# 3w-rgb-led-connector-mk-2_0.net
KiCad netlist of a schematic drawn in EAGLE
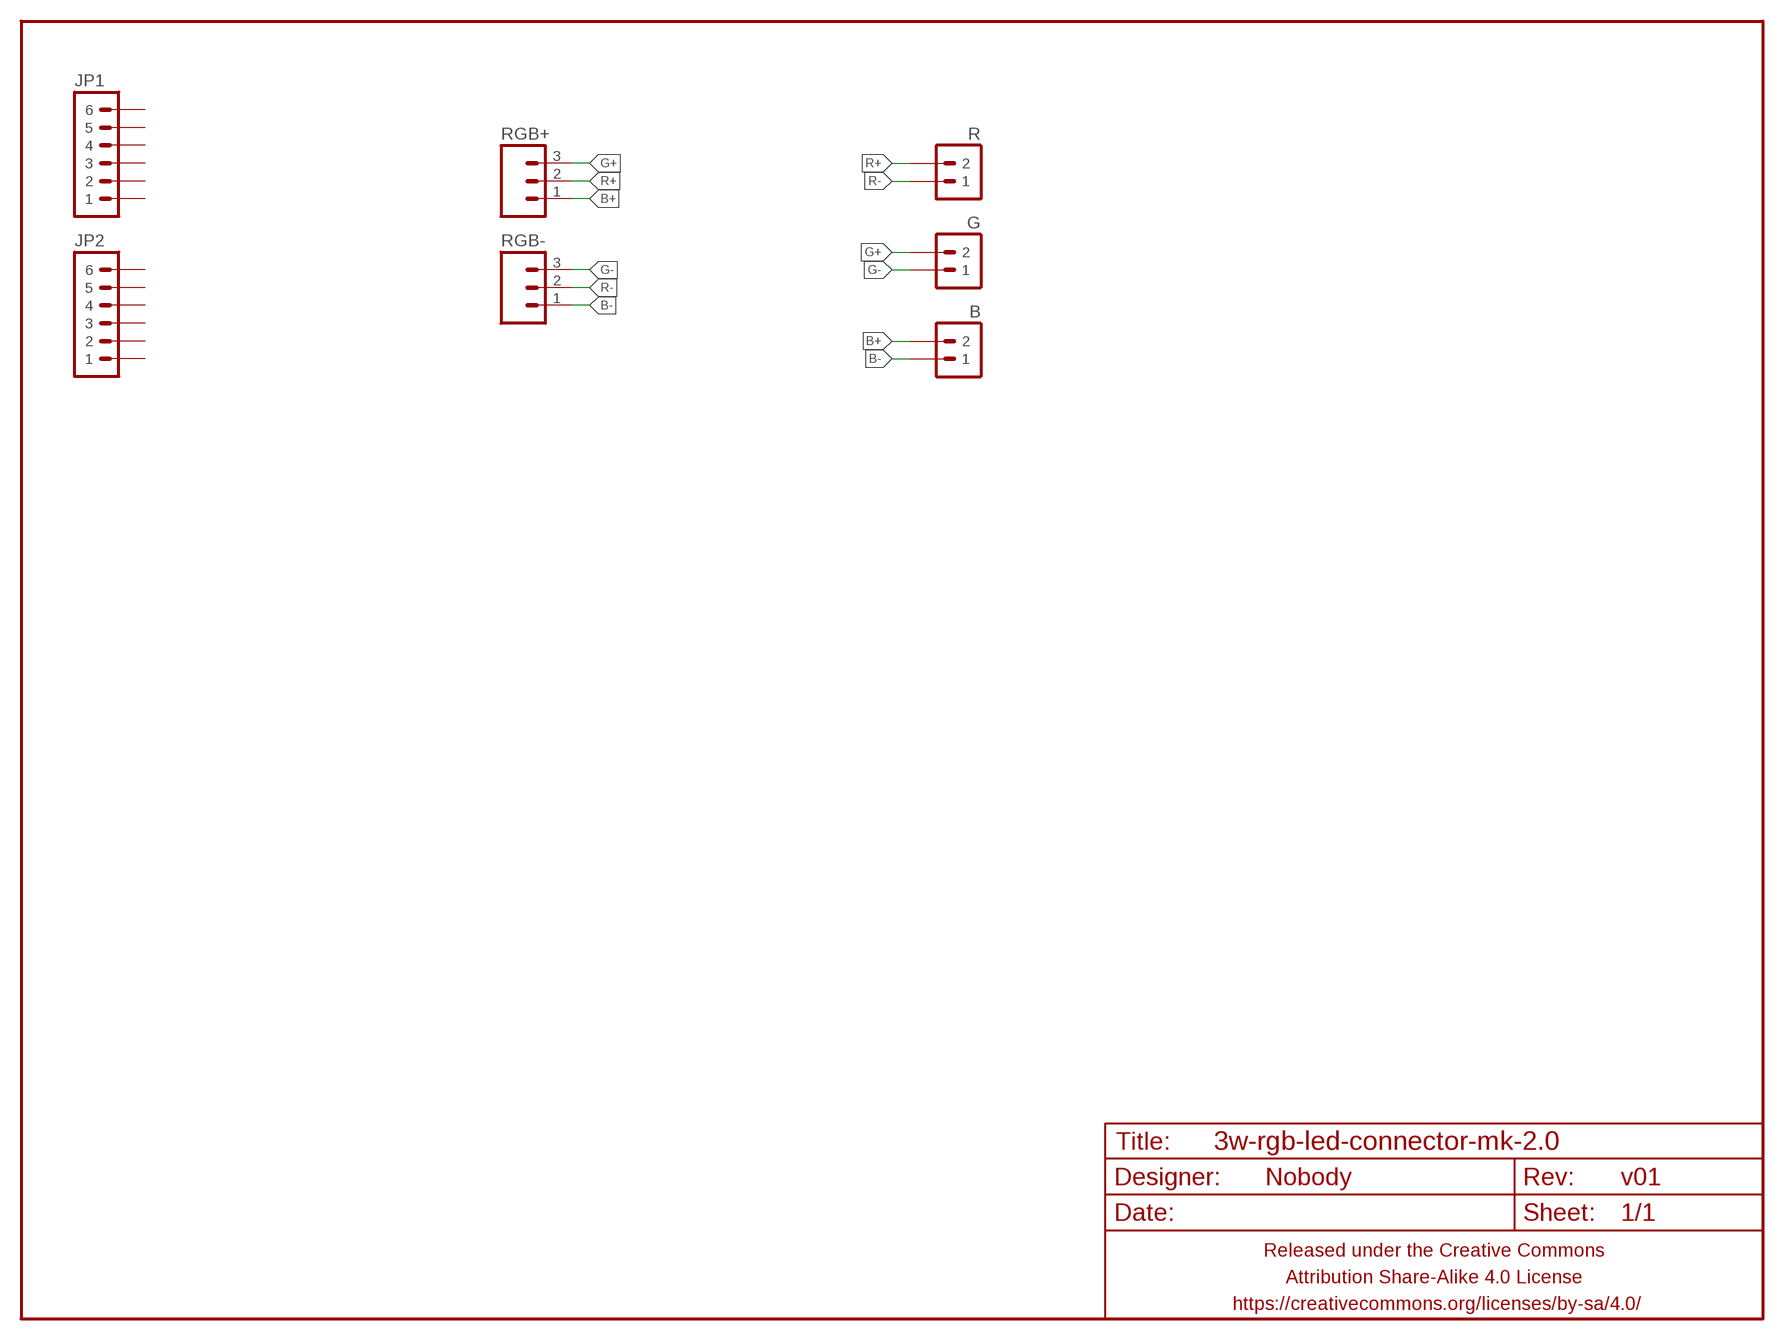
[diagram p0: schematic, sheet 1]

(export (version "E")
  (design (tool "Eeschema 10.0.6"))
  (components
    (comp (ref "B")
      (value "M023.5MM-NO_SILK")
      (footprint "eagle-import:SCREWTERMINAL-3.5MM-2-NS")
      (libsource (lib "eagle-import") (part "M023.5MM-NO_SILK"))
    )
    (comp (ref "FRAME1")
      (value "FRAME-LETTERNO_PACKAGE")
      (footprint "eagle-import:DUMMY")
      (fields (field (name "DESIGNER") "Nobody"))
      (libsource (lib "eagle-import") (part "FRAME-LETTERNO_PACKAGE"))
    )
    (comp (ref "G")
      (value "M023.5MM-NO_SILK")
      (footprint "eagle-import:SCREWTERMINAL-3.5MM-2-NS")
      (libsource (lib "eagle-import") (part "M023.5MM-NO_SILK"))
    )
    (comp (ref "JP1")
      (value "M06SIP")
      (footprint "eagle-import:1X06")
      (libsource (lib "eagle-import") (part "M06SIP"))
    )
    (comp (ref "JP2")
      (value "M06SIP")
      (footprint "eagle-import:1X06")
      (libsource (lib "eagle-import") (part "M06SIP"))
    )
    (comp (ref "R")
      (value "M023.5MM-NO_SILK")
      (footprint "eagle-import:SCREWTERMINAL-3.5MM-2-NS")
      (libsource (lib "eagle-import") (part "M023.5MM-NO_SILK"))
    )
    (comp (ref "RGB+")
      (value "M03JST-XH-RA-PTH")
      (footprint "eagle-import:JST-3-XH-RA-PTH")
      (libsource (lib "eagle-import") (part "M03JST-XH-RA-PTH"))
    )
    (comp (ref "RGB-")
      (value "M03JST-XH-RA-PTH")
      (footprint "eagle-import:JST-3-XH-RA-PTH")
      (libsource (lib "eagle-import") (part "M03JST-XH-RA-PTH"))
    )
  )
  (nets
    (net (code "1") (name "B+") (class "Default")
      (node (ref "B") (pin "2") (pinfunction "2_2") (pintype "passive"))
      (node (ref "RGB+") (pin "1") (pinfunction "1_1") (pintype "passive"))
    )
    (net (code "2") (name "B-") (class "Default")
      (node (ref "B") (pin "1") (pinfunction "1_1") (pintype "passive"))
      (node (ref "RGB-") (pin "1") (pinfunction "1_1") (pintype "passive"))
    )
    (net (code "3") (name "G+") (class "Default")
      (node (ref "G") (pin "2") (pinfunction "2_2") (pintype "passive"))
      (node (ref "RGB+") (pin "3") (pinfunction "3_3") (pintype "passive"))
    )
    (net (code "4") (name "G-") (class "Default")
      (node (ref "G") (pin "1") (pinfunction "1_1") (pintype "passive"))
      (node (ref "RGB-") (pin "3") (pinfunction "3_3") (pintype "passive"))
    )
    (net (code "5") (name "R+") (class "Default")
      (node (ref "R") (pin "2") (pinfunction "2_2") (pintype "passive"))
      (node (ref "RGB+") (pin "2") (pinfunction "2_2") (pintype "passive"))
    )
    (net (code "6") (name "R-") (class "Default")
      (node (ref "R") (pin "1") (pinfunction "1_1") (pintype "passive"))
      (node (ref "RGB-") (pin "2") (pinfunction "2_2") (pintype "passive"))
    )
    (net (code "7") (name "unconnected-(JP1-Pad1)") (class "Default")
      (node (ref "JP1") (pin "1") (pinfunction "1_1") (pintype "passive"))
    )
    (net (code "8") (name "unconnected-(JP1-Pad2)") (class "Default")
      (node (ref "JP1") (pin "2") (pinfunction "2_2") (pintype "passive"))
    )
    (net (code "9") (name "unconnected-(JP1-Pad3)") (class "Default")
      (node (ref "JP1") (pin "3") (pinfunction "3_3") (pintype "passive"))
    )
    (net (code "10") (name "unconnected-(JP1-Pad4)") (class "Default")
      (node (ref "JP1") (pin "4") (pinfunction "4_4") (pintype "passive"))
    )
    (net (code "11") (name "unconnected-(JP1-Pad5)") (class "Default")
      (node (ref "JP1") (pin "5") (pinfunction "5_5") (pintype "passive"))
    )
    (net (code "12") (name "unconnected-(JP1-Pad6)") (class "Default")
      (node (ref "JP1") (pin "6") (pinfunction "6_6") (pintype "passive"))
    )
    (net (code "13") (name "unconnected-(JP2-Pad1)") (class "Default")
      (node (ref "JP2") (pin "1") (pinfunction "1_1") (pintype "passive"))
    )
    (net (code "14") (name "unconnected-(JP2-Pad2)") (class "Default")
      (node (ref "JP2") (pin "2") (pinfunction "2_2") (pintype "passive"))
    )
    (net (code "15") (name "unconnected-(JP2-Pad3)") (class "Default")
      (node (ref "JP2") (pin "3") (pinfunction "3_3") (pintype "passive"))
    )
    (net (code "16") (name "unconnected-(JP2-Pad4)") (class "Default")
      (node (ref "JP2") (pin "4") (pinfunction "4_4") (pintype "passive"))
    )
    (net (code "17") (name "unconnected-(JP2-Pad5)") (class "Default")
      (node (ref "JP2") (pin "5") (pinfunction "5_5") (pintype "passive"))
    )
    (net (code "18") (name "unconnected-(JP2-Pad6)") (class "Default")
      (node (ref "JP2") (pin "6") (pinfunction "6_6") (pintype "passive"))
    )
  )
)
